# LED-driver_I2C.net
KiCad netlist of a schematic drawn in EAGLE
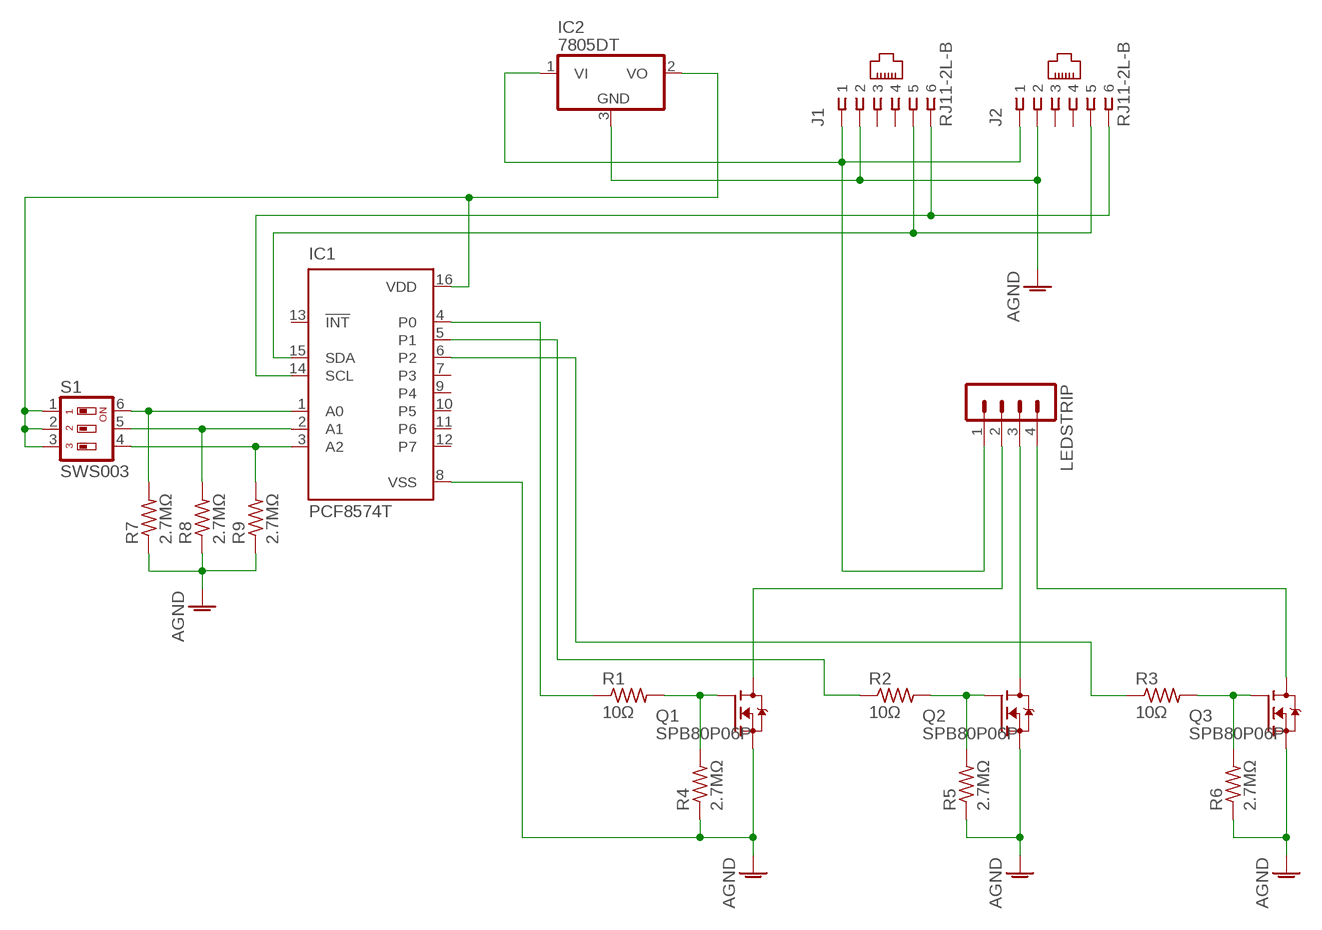
[diagram p0: schematic, sheet 1]

(export (version "E")
  (design (tool "Eeschema 10.0.6"))
  (components
    (comp (ref "IC1")
      (value "PCF8574T")
      (footprint "eagle-import:SO16W")
      (fields (field (name "MPN") "PCF8574T/3,512"))
      (libsource (lib "eagle-import") (part "PCF8574T"))
    )
    (comp (ref "IC2")
      (value "7805DT")
      (footprint "eagle-import:TO252")
      (libsource (lib "eagle-import") (part "78DT05"))
    )
    (comp (ref "J1")
      (value "RJ11-2L-B")
      (footprint "eagle-import:RJ11-NO_SHIELD")
      (fields (field (name "MF") "TYCO ELECTRONICS"))
      (libsource (lib "eagle-import") (part "RJ11-2L-B"))
    )
    (comp (ref "J2")
      (value "RJ11-2L-B")
      (footprint "eagle-import:RJ11-NO_SHIELD")
      (fields (field (name "MF") "TYCO ELECTRONICS"))
      (libsource (lib "eagle-import") (part "RJ11-2L-B"))
    )
    (comp (ref "LEDSTRIP")
      (value "MA04-1")
      (footprint "eagle-import:MA04-1")
      (libsource (lib "eagle-import") (part "MA04-1"))
    )
    (comp (ref "Q1")
      (value "SPB80P06P")
      (footprint "eagle-import:TO263")
      (libsource (lib "eagle-import") (part "SPB80P06P"))
    )
    (comp (ref "Q2")
      (value "SPB80P06P")
      (footprint "eagle-import:TO263")
      (libsource (lib "eagle-import") (part "SPB80P06P"))
    )
    (comp (ref "Q3")
      (value "SPB80P06P")
      (footprint "eagle-import:TO263")
      (libsource (lib "eagle-import") (part "SPB80P06P"))
    )
    (comp (ref "R1")
      (value "10Ω")
      (footprint "eagle-import:R0402")
      (libsource (lib "eagle-import") (part "R-US_R0402"))
    )
    (comp (ref "R2")
      (value "10Ω")
      (footprint "eagle-import:R0402")
      (libsource (lib "eagle-import") (part "R-US_R0402"))
    )
    (comp (ref "R3")
      (value "10Ω")
      (footprint "eagle-import:R0402")
      (libsource (lib "eagle-import") (part "R-US_R0402"))
    )
    (comp (ref "R4")
      (value "2.7MΩ")
      (footprint "eagle-import:R0402")
      (libsource (lib "eagle-import") (part "R-US_R0402"))
    )
    (comp (ref "R5")
      (value "2.7MΩ")
      (footprint "eagle-import:R0402")
      (libsource (lib "eagle-import") (part "R-US_R0402"))
    )
    (comp (ref "R6")
      (value "2.7MΩ")
      (footprint "eagle-import:R0402")
      (libsource (lib "eagle-import") (part "R-US_R0402"))
    )
    (comp (ref "R7")
      (value "2.7MΩ")
      (footprint "eagle-import:R0402")
      (libsource (lib "eagle-import") (part "R-US_R0402"))
    )
    (comp (ref "R8")
      (value "2.7MΩ")
      (footprint "eagle-import:R0402")
      (libsource (lib "eagle-import") (part "R-US_R0402"))
    )
    (comp (ref "R9")
      (value "2.7MΩ")
      (footprint "eagle-import:R0402")
      (libsource (lib "eagle-import") (part "R-US_R0402"))
    )
    (comp (ref "S1")
      (value "SWS003")
      (footprint "eagle-import:SMS-003")
      (libsource (lib "eagle-import") (part "SWS003"))
    )
  )
  (nets
    (net (code "1") (name "AGND") (class "Default")
      (node (ref "IC1") (pin "8") (pinfunction "VSS_8") (pintype "power_in"))
      (node (ref "IC2") (pin "3") (pinfunction "GND_3") (pintype "passive"))
      (node (ref "J1") (pin "2") (pinfunction "2_2") (pintype "passive"))
      (node (ref "J2") (pin "2") (pinfunction "2_2") (pintype "passive"))
      (node (ref "Q1") (pin "2") (pinfunction "D_2") (pintype "passive"))
      (node (ref "Q2") (pin "2") (pinfunction "D_2") (pintype "passive"))
      (node (ref "Q3") (pin "2") (pinfunction "D_2") (pintype "passive"))
      (node (ref "R4") (pin "1") (pinfunction "1_1") (pintype "passive"))
      (node (ref "R5") (pin "1") (pinfunction "1_1") (pintype "passive"))
      (node (ref "R6") (pin "1") (pinfunction "1_1") (pintype "passive"))
      (node (ref "R7") (pin "1") (pinfunction "1_1") (pintype "passive"))
      (node (ref "R8") (pin "1") (pinfunction "1_1") (pintype "passive"))
      (node (ref "R9") (pin "1") (pinfunction "1_1") (pintype "passive"))
    )
    (net (code "2") (name "Net-(IC1-A0)") (class "Default")
      (node (ref "IC1") (pin "1") (pinfunction "A0_1") (pintype "input"))
      (node (ref "R7") (pin "2") (pinfunction "2_2") (pintype "passive"))
      (node (ref "S1") (pin "6") (pinfunction "6_6") (pintype "passive"))
    )
    (net (code "3") (name "Net-(IC1-A1)") (class "Default")
      (node (ref "IC1") (pin "2") (pinfunction "A1_2") (pintype "input"))
      (node (ref "R8") (pin "2") (pinfunction "2_2") (pintype "passive"))
      (node (ref "S1") (pin "5") (pinfunction "5_5") (pintype "passive"))
    )
    (net (code "4") (name "Net-(IC1-A2)") (class "Default")
      (node (ref "IC1") (pin "3") (pinfunction "A2_3") (pintype "input"))
      (node (ref "R9") (pin "2") (pinfunction "2_2") (pintype "passive"))
      (node (ref "S1") (pin "4") (pinfunction "4_4") (pintype "passive"))
    )
    (net (code "5") (name "Net-(IC1-P0)") (class "Default")
      (node (ref "IC1") (pin "4") (pinfunction "P0_4") (pintype "bidirectional"))
      (node (ref "R1") (pin "1") (pinfunction "1_1") (pintype "passive"))
    )
    (net (code "6") (name "Net-(IC1-P1)") (class "Default")
      (node (ref "IC1") (pin "5") (pinfunction "P1_5") (pintype "bidirectional"))
      (node (ref "R2") (pin "1") (pinfunction "1_1") (pintype "passive"))
    )
    (net (code "7") (name "Net-(IC1-P2)") (class "Default")
      (node (ref "IC1") (pin "6") (pinfunction "P2_6") (pintype "bidirectional"))
      (node (ref "R3") (pin "1") (pinfunction "1_1") (pintype "passive"))
    )
    (net (code "8") (name "Net-(IC1-SCL)") (class "Default")
      (node (ref "IC1") (pin "14") (pinfunction "SCL_14") (pintype "input"))
      (node (ref "J1") (pin "6") (pinfunction "6_6") (pintype "passive"))
      (node (ref "J2") (pin "6") (pinfunction "6_6") (pintype "passive"))
    )
    (net (code "9") (name "Net-(IC1-SDA)") (class "Default")
      (node (ref "IC1") (pin "15") (pinfunction "SDA_15") (pintype "bidirectional"))
      (node (ref "J1") (pin "5") (pinfunction "5_5") (pintype "passive"))
      (node (ref "J2") (pin "5") (pinfunction "5_5") (pintype "passive"))
    )
    (net (code "10") (name "Net-(IC1-VDD)") (class "Default")
      (node (ref "IC1") (pin "16") (pinfunction "VDD_16") (pintype "power_in"))
      (node (ref "IC2") (pin "2") (pinfunction "VO_2") (pintype "passive"))
      (node (ref "S1") (pin "1") (pinfunction "1_1") (pintype "passive"))
      (node (ref "S1") (pin "2") (pinfunction "2_2") (pintype "passive"))
      (node (ref "S1") (pin "3") (pinfunction "3_3") (pintype "passive"))
    )
    (net (code "11") (name "Net-(IC2-VI)") (class "Default")
      (node (ref "IC2") (pin "1") (pinfunction "VI_1") (pintype "input"))
      (node (ref "J1") (pin "1") (pinfunction "1_1") (pintype "passive"))
      (node (ref "J2") (pin "1") (pinfunction "1_1") (pintype "passive"))
      (node (ref "LEDSTRIP") (pin "1") (pinfunction "1_1") (pintype "passive"))
    )
    (net (code "12") (name "Net-(Q1-G)") (class "Default")
      (node (ref "Q1") (pin "1") (pinfunction "G_1") (pintype "passive"))
      (node (ref "R1") (pin "2") (pinfunction "2_2") (pintype "passive"))
      (node (ref "R4") (pin "2") (pinfunction "2_2") (pintype "passive"))
    )
    (net (code "13") (name "Net-(Q1-S)") (class "Default")
      (node (ref "LEDSTRIP") (pin "2") (pinfunction "2_2") (pintype "passive"))
      (node (ref "Q1") (pin "3") (pinfunction "S_3") (pintype "passive"))
    )
    (net (code "14") (name "Net-(Q2-G)") (class "Default")
      (node (ref "Q2") (pin "1") (pinfunction "G_1") (pintype "passive"))
      (node (ref "R2") (pin "2") (pinfunction "2_2") (pintype "passive"))
      (node (ref "R5") (pin "2") (pinfunction "2_2") (pintype "passive"))
    )
    (net (code "15") (name "Net-(Q2-S)") (class "Default")
      (node (ref "LEDSTRIP") (pin "3") (pinfunction "3_3") (pintype "passive"))
      (node (ref "Q2") (pin "3") (pinfunction "S_3") (pintype "passive"))
    )
    (net (code "16") (name "Net-(Q3-G)") (class "Default")
      (node (ref "Q3") (pin "1") (pinfunction "G_1") (pintype "passive"))
      (node (ref "R3") (pin "2") (pinfunction "2_2") (pintype "passive"))
      (node (ref "R6") (pin "2") (pinfunction "2_2") (pintype "passive"))
    )
    (net (code "17") (name "Net-(Q3-S)") (class "Default")
      (node (ref "LEDSTRIP") (pin "4") (pinfunction "4_4") (pintype "passive"))
      (node (ref "Q3") (pin "3") (pinfunction "S_3") (pintype "passive"))
    )
    (net (code "18") (name "unconnected-(IC1-P3-Pad7)") (class "Default")
      (node (ref "IC1") (pin "7") (pinfunction "P3_7") (pintype "bidirectional"))
    )
    (net (code "19") (name "unconnected-(IC1-P4-Pad9)") (class "Default")
      (node (ref "IC1") (pin "9") (pinfunction "P4_9") (pintype "bidirectional"))
    )
    (net (code "20") (name "unconnected-(IC1-P5-Pad10)") (class "Default")
      (node (ref "IC1") (pin "10") (pinfunction "P5_10") (pintype "bidirectional"))
    )
    (net (code "21") (name "unconnected-(IC1-P6-Pad11)") (class "Default")
      (node (ref "IC1") (pin "11") (pinfunction "P6_11") (pintype "bidirectional"))
    )
    (net (code "22") (name "unconnected-(IC1-P7-Pad12)") (class "Default")
      (node (ref "IC1") (pin "12") (pinfunction "P7_12") (pintype "bidirectional"))
    )
    (net (code "23") (name "unconnected-(IC1-~{INT}-Pad13)") (class "Default")
      (node (ref "IC1") (pin "13") (pinfunction "~{INT}_13") (pintype "output"))
    )
    (net (code "24") (name "unconnected-(J1-Pad3)") (class "Default")
      (node (ref "J1") (pin "3") (pinfunction "3_3") (pintype "passive"))
    )
    (net (code "25") (name "unconnected-(J1-Pad4)") (class "Default")
      (node (ref "J1") (pin "4") (pinfunction "4_4") (pintype "passive"))
    )
    (net (code "26") (name "unconnected-(J2-Pad3)") (class "Default")
      (node (ref "J2") (pin "3") (pinfunction "3_3") (pintype "passive"))
    )
    (net (code "27") (name "unconnected-(J2-Pad4)") (class "Default")
      (node (ref "J2") (pin "4") (pinfunction "4_4") (pintype "passive"))
    )
  )
)
